# Power_Regulation.net
KiCad netlist of a schematic drawn in Altium Designer
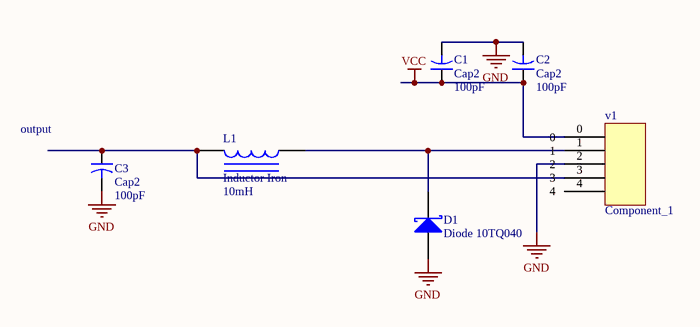
[diagram p0: Power Regulation.SchDoc]

(export (version "E")
  (design (tool "Eeschema 10.0.6"))
  (components
    (comp (ref "C1")
      (value "Cap2")
      (footprint "CAPR5-4X5")
      (description "Capacitor")
      (fields (field (name "ALTIUM_VALUE") "100pF") (field (name "PUBLISHER") "Altium Limited"))
      (libsource (lib "Miscellaneous Devices") (part "Cap2"))
    )
    (comp (ref "C2")
      (value "Cap2")
      (footprint "CAPR5-4X5")
      (description "Capacitor")
      (fields (field (name "ALTIUM_VALUE") "100pF") (field (name "PUBLISHER") "Altium Limited"))
      (libsource (lib "Miscellaneous Devices") (part "Cap2"))
    )
    (comp (ref "C3")
      (value "Cap2")
      (footprint "CAPR5-4X5")
      (description "Capacitor")
      (fields (field (name "ALTIUM_VALUE") "100pF") (field (name "PUBLISHER") "Altium Limited"))
      (libsource (lib "Miscellaneous Devices") (part "Cap2"))
    )
    (comp (ref "D1")
      (value "Diode 10TQ040")
      (footprint "TO-220AC")
      (description "Schottky Rectifier")
      (fields (field (name "PUBLISHER") "Altium Limited"))
      (libsource (lib "Miscellaneous Devices") (part "Diode 10TQ040"))
    )
    (comp (ref "L1")
      (value "Inductor Iron")
      (footprint "AXIAL-0.9")
      (description "Magnetic-Core Inductor")
      (fields (field (name "ALTIUM_VALUE") "10mH") (field (name "PUBLISHER") "Altium Limited"))
      (libsource (lib "Miscellaneous Devices") (part "Inductor Iron"))
    )
    (comp (ref "v1")
      (value "Component_1")
      (footprint "Model Name")
      (libsource (lib "voltage regulator") (part "Component_1"))
    )
  )
  (nets
    (net (code "1") (name "GND") (class "Default")
      (node (ref "C1") (pin "2") (pinfunction "2_2") (pintype "passive"))
      (node (ref "C2") (pin "2") (pinfunction "2_2") (pintype "passive"))
      (node (ref "C3") (pin "2") (pinfunction "2_2") (pintype "passive"))
      (node (ref "D1") (pin "3") (pinfunction "A_3") (pintype "passive"))
    )
    (net (code "2") (name "Net-(C3-Pad1)") (class "Default")
      (node (ref "C3") (pin "1") (pinfunction "1_1") (pintype "passive"))
      (node (ref "L1") (pin "2") (pinfunction "2_2") (pintype "passive"))
    )
    (net (code "3") (name "Net-(D1-K)") (class "Default")
      (node (ref "D1") (pin "1") (pinfunction "K_1") (pintype "passive"))
      (node (ref "L1") (pin "1") (pinfunction "1_1") (pintype "passive"))
    )
    (net (code "4") (name "VCC") (class "Default")
      (node (ref "C1") (pin "1") (pinfunction "1_1") (pintype "passive"))
      (node (ref "C2") (pin "1") (pinfunction "1_1") (pintype "passive"))
    )
    (net (code "5") (name "unconnected-(v1-Pad0)") (class "Default")
      (node (ref "v1") (pin "0") (pinfunction "0_0") (pintype "passive"))
    )
    (net (code "6") (name "unconnected-(v1-Pad1)") (class "Default")
      (node (ref "v1") (pin "1") (pinfunction "1_1") (pintype "passive"))
    )
    (net (code "7") (name "unconnected-(v1-Pad2)") (class "Default")
      (node (ref "v1") (pin "2") (pinfunction "2_2") (pintype "passive"))
    )
    (net (code "8") (name "unconnected-(v1-Pad3)") (class "Default")
      (node (ref "v1") (pin "3") (pinfunction "3_3") (pintype "passive"))
    )
    (net (code "9") (name "unconnected-(v1-Pad4)") (class "Default")
      (node (ref "v1") (pin "4") (pinfunction "4_4") (pintype "passive"))
    )
  )
)
